# MCU.net
KiCad netlist of a schematic drawn in Altium Designer
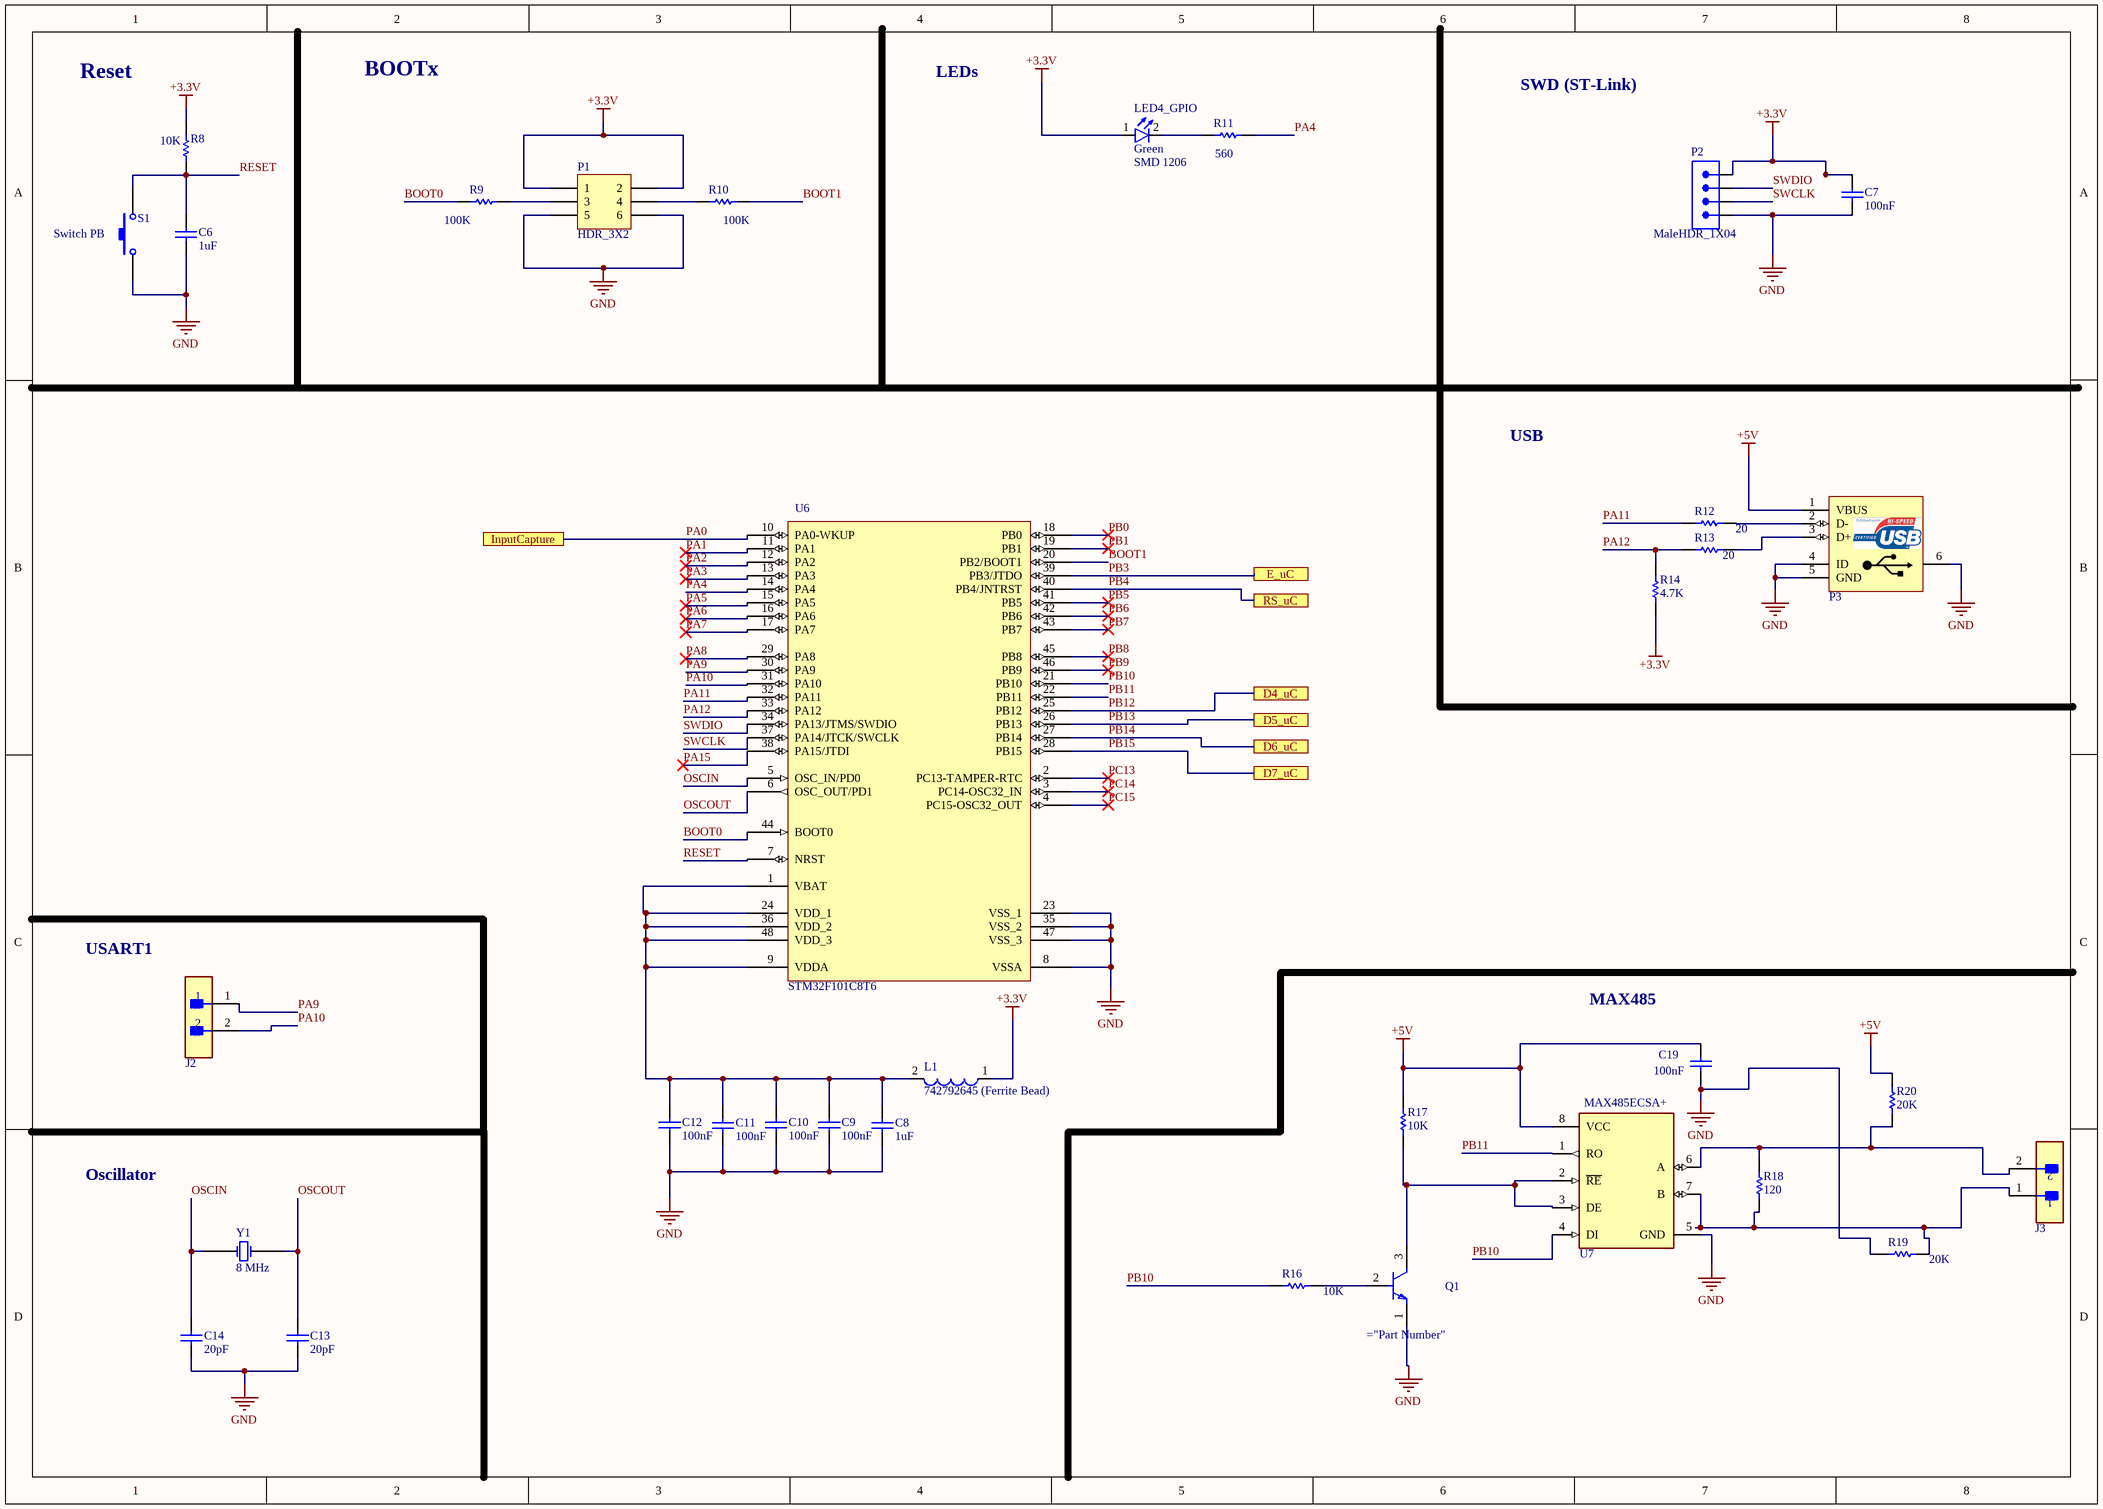
[diagram p0: MCU.SchDoc]

(export (version "E")
  (design (tool "Eeschema 10.0.6"))
  (components
    (comp (ref "C6")
      (value "1uF")
      (footprint "CAPC3216L (1206)")
      (description "Bipolar Capacitor")
      (fields
        (field (name "VOLTAGE") "100V")
        (field (name "DESIGNER") "Eng. Saeid Jorablo")
        (field (name "PUBLISHER") "SJ Unlimited")
      )
      (libsource (lib "Passive Components") (part "CAP_Bipolar"))
    )
    (comp (ref "C7")
      (value "100nF")
      (footprint "CAPC3216L (1206)")
      (description "Bipolar Capacitor")
      (fields
        (field (name "VOLTAGE") "100V")
        (field (name "DESIGNER") "Eng. Saeid Jorablo")
        (field (name "PUBLISHER") "SJ Unlimited")
      )
      (libsource (lib "Passive Components") (part "CAP_Bipolar"))
    )
    (comp (ref "C8")
      (value "1uF")
      (footprint "Cap - 100nF")
      (description "Bipolar Capacitor")
      (fields
        (field (name "VOLTAGE") "100V")
        (field (name "DESIGNER") "Eng. Saeid Jorablo")
        (field (name "PUBLISHER") "SJ Unlimited")
      )
      (libsource (lib "Passive Components") (part "CAP_Bipolar"))
    )
    (comp (ref "C9")
      (value "100nF")
      (footprint "CAPC3216M (1206)")
      (description "Bipolar Capacitor")
      (fields
        (field (name "VOLTAGE") "100V")
        (field (name "DESIGNER") "Eng. Saeid Jorablo")
        (field (name "PUBLISHER") "SJ Unlimited")
      )
      (libsource (lib "Passive Components") (part "CAP_Bipolar"))
    )
    (comp (ref "C10")
      (value "100nF")
      (footprint "CAPC3216M (1206)")
      (description "Bipolar Capacitor")
      (fields
        (field (name "VOLTAGE") "100V")
        (field (name "DESIGNER") "Eng. Saeid Jorablo")
        (field (name "PUBLISHER") "SJ Unlimited")
      )
      (libsource (lib "Passive Components") (part "CAP_Bipolar"))
    )
    (comp (ref "C11")
      (value "100nF")
      (footprint "CAPC3216M (1206)")
      (description "Bipolar Capacitor")
      (fields
        (field (name "VOLTAGE") "100V")
        (field (name "DESIGNER") "Eng. Saeid Jorablo")
        (field (name "PUBLISHER") "SJ Unlimited")
      )
      (libsource (lib "Passive Components") (part "CAP_Bipolar"))
    )
    (comp (ref "C12")
      (value "100nF")
      (footprint "CAPC3216M (1206)")
      (description "Bipolar Capacitor")
      (fields
        (field (name "VOLTAGE") "100V")
        (field (name "DESIGNER") "Eng. Saeid Jorablo")
        (field (name "PUBLISHER") "SJ Unlimited")
      )
      (libsource (lib "Passive Components") (part "CAP_Bipolar"))
    )
    (comp (ref "C13")
      (value "20pF")
      (footprint "CAPC1608M (0603)")
      (description "Bipolar Capacitor")
      (fields
        (field (name "VOLTAGE") "100V")
        (field (name "DESIGNER") "Eng. Saeid Jorablo")
        (field (name "PUBLISHER") "SJ Unlimited")
      )
      (libsource (lib "Passive Components") (part "CAP_Bipolar"))
    )
    (comp (ref "C14")
      (value "20pF")
      (footprint "CAPC1608M (0603)")
      (description "Bipolar Capacitor")
      (fields
        (field (name "VOLTAGE") "100V")
        (field (name "DESIGNER") "Eng. Saeid Jorablo")
        (field (name "PUBLISHER") "SJ Unlimited")
      )
      (libsource (lib "Passive Components") (part "CAP_Bipolar"))
    )
    (comp (ref "C19")
      (value "100nF")
      (footprint "CAPC3216M (1206)")
      (description "Bipolar Capacitor")
      (fields
        (field (name "VOLTAGE") "100V")
        (field (name "DESIGNER") "Eng. Saeid Jorablo")
        (field (name "PUBLISHER") "SJ Unlimited")
      )
      (libsource (lib "Passive Components") (part "CAP_Bipolar"))
    )
    (comp (ref "J2")
      (value "B2B-XH-A_LF_SN")
      (footprint "JST_0_MFG")
      (libsource (lib "") (part "B2B-XH-A_LF_SN_1"))
    )
    (comp (ref "J3")
      (value "B2B-XH-A_LF_SN")
      (footprint "JST_0_MFG")
      (libsource (lib "Amir_Lib") (part "B2B-XH-A_LF_SN"))
    )
    (comp (ref "L1")
      (value "742792645 (Ferrite Bead)")
      (footprint "SMD-0603")
      (description "SMD EMI Suppression Ferrite Bead WE-CBF, Z = 470 Ohm")
      (libsource (lib "Wuerth Elektronik EMC Ferrite") (part "742792645"))
    )
    (comp (ref "LED4_GPIO")
      (value "Green")
      (footprint "LED SMD 1206")
      (description "LED")
      (fields
        (field (name "COLOR") "Green")
        (field (name "SIZE") "SMD 1206")
        (field (name "DESIGNER") "Saeid Jorablo")
      )
      (libsource (lib "General 2") (part "LED"))
    )
    (comp (ref "P1")
      (value "HDR_3X2")
      (footprint "MISC_HDR_2X3")
      (description "Header, 3-Pin, Dual row")
      (fields (field (name "PUBLISHER") "SJ UnLimited") (field (name "DESIGNER") "Eng. Saeid Jorablo"))
      (libsource (lib "Sockets And Connectors") (part "HDR_3X2"))
    )
    (comp (ref "P2")
      (value "MaleHDR_1X04")
      (footprint "MHDR1X04-254P")
      (description "Male Header 1X04")
      (libsource (lib "Sockets And Connectors") (part "MHDR_1X04"))
    )
    (comp (ref "P3")
      (value "USB Connector")
      (footprint "USB_AB_BM_SHS")
      (description "USB MICRO-B Type Connector")
      (fields (field (name "DESIGNER") "ABBAS BASEREH") (field (name "PUBLISHER") "ABBAS BASEREH"))
      (libsource (lib "General 1") (part "USB AB MICRO CONNECTOR"))
    )
    (comp (ref "Q1")
      (value "2N3904TF")
      (footprint "ON_Semiconductor_135AR_MFG")
      (libsource (lib "Amir_Lib") (part "2N3904TF"))
    )
    (comp (ref "R8")
      (value "10K")
      (footprint "RESC3216X60L (1206)")
      (description "Resistor")
      (fields
        (field (name "TOLERANCE") "5%")
        (field (name "POWER") "1/8 W")
        (field (name "DESIGNER") "Eng. Saeid Jorablo")
        (field (name "PUBLISHER") "SJ Unlimited")
      )
      (libsource (lib "Passive Components") (part "RES"))
    )
    (comp (ref "R9")
      (value "100K")
      (footprint "RESC3216X60M (1206)")
      (description "Resistor")
      (fields
        (field (name "TOLERANCE") "5%")
        (field (name "POWER") "1/8 W")
        (field (name "DESIGNER") "Eng. Saeid Jorablo")
        (field (name "PUBLISHER") "SJ Unlimited")
      )
      (libsource (lib "Passive Components") (part "RES"))
    )
    (comp (ref "R10")
      (value "100K")
      (footprint "RESC3216X60M (1206)")
      (description "Resistor")
      (fields
        (field (name "TOLERANCE") "5%")
        (field (name "POWER") "1/8 W")
        (field (name "DESIGNER") "Eng. Saeid Jorablo")
        (field (name "PUBLISHER") "SJ Unlimited")
      )
      (libsource (lib "Passive Components") (part "RES"))
    )
    (comp (ref "R11")
      (value "560")
      (footprint "RESC3216X60M (1206)")
      (description "Resistor")
      (fields
        (field (name "TOLERANCE") "5%")
        (field (name "POWER") "1/8 W")
        (field (name "DESIGNER") "Eng. Saeid Jorablo")
        (field (name "PUBLISHER") "SJ Unlimited")
      )
      (libsource (lib "Passive Components") (part "RES"))
    )
    (comp (ref "R12")
      (value "20")
      (footprint "RESC3216X60M (1206)")
      (description "Resistor")
      (fields
        (field (name "TOLERANCE") "5%")
        (field (name "POWER") "1/8 W")
        (field (name "DESIGNER") "Eng. Saeid Jorablo")
        (field (name "PUBLISHER") "SJ Unlimited")
      )
      (libsource (lib "Passive Components") (part "RES"))
    )
    (comp (ref "R13")
      (value "20")
      (footprint "RESC3216X60M (1206)")
      (description "Resistor")
      (fields
        (field (name "TOLERANCE") "5%")
        (field (name "POWER") "1/8 W")
        (field (name "DESIGNER") "Eng. Saeid Jorablo")
        (field (name "PUBLISHER") "SJ Unlimited")
      )
      (libsource (lib "Passive Components") (part "RES"))
    )
    (comp (ref "R14")
      (value "4.7K")
      (footprint "RESC3216X60M (1206)")
      (description "Resistor")
      (fields
        (field (name "TOLERANCE") "5%")
        (field (name "POWER") "1/8 W")
        (field (name "DESIGNER") "Eng. Saeid Jorablo")
        (field (name "PUBLISHER") "SJ Unlimited")
      )
      (libsource (lib "Passive Components") (part "RES"))
    )
    (comp (ref "R16")
      (value "10K")
      (footprint "RESC3216X60M (1206)")
      (description "Resistor")
      (fields
        (field (name "TOLERANCE") "5%")
        (field (name "POWER") "1/8 W")
        (field (name "DESIGNER") "Eng. Saeid Jorablo")
        (field (name "PUBLISHER") "SJ Unlimited")
      )
      (libsource (lib "Passive Components") (part "RES"))
    )
    (comp (ref "R17")
      (value "10K")
      (footprint "RESC3216X60M (1206)")
      (description "Resistor")
      (fields
        (field (name "TOLERANCE") "5%")
        (field (name "POWER") "1/8 W")
        (field (name "DESIGNER") "Eng. Saeid Jorablo")
        (field (name "PUBLISHER") "SJ Unlimited")
      )
      (libsource (lib "Passive Components") (part "RES"))
    )
    (comp (ref "R18")
      (value "120")
      (footprint "RESC3216X60M (1206)")
      (description "Resistor")
      (fields
        (field (name "TOLERANCE") "5%")
        (field (name "POWER") "1/8 W")
        (field (name "DESIGNER") "Eng. Saeid Jorablo")
        (field (name "PUBLISHER") "SJ Unlimited")
      )
      (libsource (lib "Passive Components") (part "RES"))
    )
    (comp (ref "R19")
      (value "20K")
      (footprint "RESC3216X60M (1206)")
      (description "Resistor")
      (fields
        (field (name "TOLERANCE") "5%")
        (field (name "POWER") "1/8 W")
        (field (name "DESIGNER") "Eng. Saeid Jorablo")
        (field (name "PUBLISHER") "SJ Unlimited")
      )
      (libsource (lib "Passive Components") (part "RES"))
    )
    (comp (ref "R20")
      (value "20K")
      (footprint "RESC3216X60M (1206)")
      (description "Resistor")
      (fields
        (field (name "TOLERANCE") "5%")
        (field (name "POWER") "1/8 W")
        (field (name "DESIGNER") "Eng. Saeid Jorablo")
        (field (name "PUBLISHER") "SJ Unlimited")
      )
      (libsource (lib "Passive Components") (part "RES"))
    )
    (comp (ref "S1")
      (value "Switch PB")
      (footprint "Switch - Push to On")
      (description "Push Button Switch")
      (libsource (lib "General 2") (part "Switch PB"))
    )
    (comp (ref "U6")
      (value "STM32F101C8T6")
      (footprint "LQFP48_L")
      (description "STM32 ARM-based 32-bit MCU with 64 Kbytes Flash, 48-pin LQFP, Industrial Temperature")
      (fields (field (name "PUBLISHER") "Altium Limited"))
      (libsource (lib "ST Microcontroller 32-Bit STM32") (part "STM32F101C8T6"))
    )
    (comp (ref "U7")
      (value "MAX485ECSA+")
      (footprint "Maxim_Integrated_S8-5_MFG")
      (libsource (lib "Amir_Lib") (part "MAX485ECSA+"))
    )
    (comp (ref "Y1")
      (value "8 MHz")
      (footprint "Crystal SMD")
      (description "XTAL Crystal")
      (fields (field (name "DESIGNER") "ABBAS BASEREH"))
      (libsource (lib "General 1") (part "XTAL_Crystal"))
    )
  )
  (nets
    (net (code "1") (name "+3.3V") (class "Default")
      (node (ref "C7") (pin "1") (pinfunction "+_1") (pintype "passive"))
      (node (ref "L1") (pin "1") (pinfunction "1_1") (pintype "passive"))
      (node (ref "LED4_GPIO") (pin "1") (pinfunction "A_1") (pintype "passive"))
      (node (ref "P1") (pin "1") (pinfunction "1_1") (pintype "passive"))
      (node (ref "P1") (pin "2") (pinfunction "2_2") (pintype "passive"))
      (node (ref "P2") (pin "4") (pinfunction "4_4") (pintype "passive"))
      (node (ref "R14") (pin "1") (pinfunction "1_1") (pintype "passive"))
      (node (ref "R8") (pin "2") (pinfunction "2_2") (pintype "passive"))
    )
    (net (code "2") (name "+5V") (class "Default")
      (node (ref "C19") (pin "2") (pinfunction "-_2") (pintype "passive"))
      (node (ref "P3") (pin "1") (pinfunction "VBUS_1") (pintype "power_in"))
      (node (ref "R17") (pin "2") (pinfunction "2_2") (pintype "passive"))
      (node (ref "R20") (pin "2") (pinfunction "2_2") (pintype "passive"))
      (node (ref "U7") (pin "8") (pinfunction "VCC_8") (pintype "power_in"))
    )
    (net (code "3") (name "/BOOT0") (class "Default")
      (node (ref "R9") (pin "1") (pinfunction "1_1") (pintype "passive"))
      (node (ref "U6") (pin "44") (pinfunction "BOOT0_44") (pintype "input"))
    )
    (net (code "4") (name "/BOOT1") (class "Default")
      (node (ref "R10") (pin "2") (pinfunction "2_2") (pintype "passive"))
      (node (ref "U6") (pin "20") (pinfunction "PB2/BOOT1_20") (pintype "bidirectional"))
    )
    (net (code "5") (name "/OSCIN") (class "Default")
      (node (ref "C14") (pin "1") (pinfunction "+_1") (pintype "passive"))
      (node (ref "U6") (pin "5") (pinfunction "OSC_IN/PD0_5") (pintype "input"))
      (node (ref "Y1") (pin "1") (pinfunction "OSC1_1") (pintype "passive"))
    )
    (net (code "6") (name "/OSCOUT") (class "Default")
      (node (ref "C13") (pin "1") (pinfunction "+_1") (pintype "passive"))
      (node (ref "U6") (pin "6") (pinfunction "OSC_OUT/PD1_6") (pintype "output"))
      (node (ref "Y1") (pin "2") (pinfunction "OSC2_2") (pintype "passive"))
    )
    (net (code "7") (name "/PA0") (class "Default")
      (node (ref "U6") (pin "10") (pinfunction "PA0-WKUP_10") (pintype "bidirectional"))
    )
    (net (code "8") (name "/PA1") (class "Default")
      (node (ref "U6") (pin "11") (pinfunction "PA1_11") (pintype "bidirectional+no_connect"))
    )
    (net (code "9") (name "/PA2") (class "Default")
      (node (ref "U6") (pin "12") (pinfunction "PA2_12") (pintype "bidirectional+no_connect"))
    )
    (net (code "10") (name "/PA3") (class "Default")
      (node (ref "U6") (pin "13") (pinfunction "PA3_13") (pintype "bidirectional+no_connect"))
    )
    (net (code "11") (name "/PA4") (class "Default")
      (node (ref "R11") (pin "2") (pinfunction "2_2") (pintype "passive"))
      (node (ref "U6") (pin "14") (pinfunction "PA4_14") (pintype "bidirectional"))
    )
    (net (code "12") (name "/PA5") (class "Default")
      (node (ref "U6") (pin "15") (pinfunction "PA5_15") (pintype "bidirectional+no_connect"))
    )
    (net (code "13") (name "/PA6") (class "Default")
      (node (ref "U6") (pin "16") (pinfunction "PA6_16") (pintype "bidirectional+no_connect"))
    )
    (net (code "14") (name "/PA7") (class "Default")
      (node (ref "U6") (pin "17") (pinfunction "PA7_17") (pintype "bidirectional+no_connect"))
    )
    (net (code "15") (name "/PA8") (class "Default")
      (node (ref "U6") (pin "29") (pinfunction "PA8_29") (pintype "bidirectional+no_connect"))
    )
    (net (code "16") (name "/PA9") (class "Default")
      (node (ref "J2") (pin "1") (pinfunction "1_1") (pintype "passive"))
      (node (ref "U6") (pin "30") (pinfunction "PA9_30") (pintype "bidirectional"))
    )
    (net (code "17") (name "/PA10") (class "Default")
      (node (ref "J2") (pin "2") (pinfunction "2_2") (pintype "passive"))
      (node (ref "U6") (pin "31") (pinfunction "PA10_31") (pintype "bidirectional"))
    )
    (net (code "18") (name "/PA11") (class "Default")
      (node (ref "R12") (pin "1") (pinfunction "1_1") (pintype "passive"))
      (node (ref "U6") (pin "32") (pinfunction "PA11_32") (pintype "bidirectional"))
    )
    (net (code "19") (name "/PA12") (class "Default")
      (node (ref "R13") (pin "1") (pinfunction "1_1") (pintype "passive"))
      (node (ref "R14") (pin "2") (pinfunction "2_2") (pintype "passive"))
      (node (ref "U6") (pin "33") (pinfunction "PA12_33") (pintype "bidirectional"))
    )
    (net (code "20") (name "/PA15") (class "Default")
      (node (ref "U6") (pin "38") (pinfunction "PA15/JTDI_38") (pintype "bidirectional+no_connect"))
    )
    (net (code "21") (name "/PB0") (class "Default")
      (node (ref "U6") (pin "18") (pinfunction "PB0_18") (pintype "bidirectional+no_connect"))
    )
    (net (code "22") (name "/PB1") (class "Default")
      (node (ref "U6") (pin "19") (pinfunction "PB1_19") (pintype "bidirectional+no_connect"))
    )
    (net (code "23") (name "/PB3") (class "Default")
      (node (ref "U6") (pin "39") (pinfunction "PB3/JTDO_39") (pintype "bidirectional"))
    )
    (net (code "24") (name "/PB4") (class "Default")
      (node (ref "U6") (pin "40") (pinfunction "PB4/JNTRST_40") (pintype "bidirectional"))
    )
    (net (code "25") (name "/PB5") (class "Default")
      (node (ref "U6") (pin "41") (pinfunction "PB5_41") (pintype "bidirectional+no_connect"))
    )
    (net (code "26") (name "/PB6") (class "Default")
      (node (ref "U6") (pin "42") (pinfunction "PB6_42") (pintype "bidirectional+no_connect"))
    )
    (net (code "27") (name "/PB7") (class "Default")
      (node (ref "U6") (pin "43") (pinfunction "PB7_43") (pintype "bidirectional+no_connect"))
    )
    (net (code "28") (name "/PB8") (class "Default")
      (node (ref "U6") (pin "45") (pinfunction "PB8_45") (pintype "bidirectional+no_connect"))
    )
    (net (code "29") (name "/PB9") (class "Default")
      (node (ref "U6") (pin "46") (pinfunction "PB9_46") (pintype "bidirectional+no_connect"))
    )
    (net (code "30") (name "/PB10") (class "Default")
      (node (ref "R16") (pin "1") (pinfunction "1_1") (pintype "passive"))
      (node (ref "U6") (pin "21") (pinfunction "PB10_21") (pintype "bidirectional"))
      (node (ref "U7") (pin "4") (pinfunction "DI_4") (pintype "input"))
    )
    (net (code "31") (name "/PB11") (class "Default")
      (node (ref "U6") (pin "22") (pinfunction "PB11_22") (pintype "bidirectional"))
      (node (ref "U7") (pin "1") (pinfunction "RO_1") (pintype "output"))
    )
    (net (code "32") (name "/PB12") (class "Default")
      (node (ref "U6") (pin "25") (pinfunction "PB12_25") (pintype "bidirectional"))
    )
    (net (code "33") (name "/PB13") (class "Default")
      (node (ref "U6") (pin "26") (pinfunction "PB13_26") (pintype "bidirectional"))
    )
    (net (code "34") (name "/PB14") (class "Default")
      (node (ref "U6") (pin "27") (pinfunction "PB14_27") (pintype "bidirectional"))
    )
    (net (code "35") (name "/PB15") (class "Default")
      (node (ref "U6") (pin "28") (pinfunction "PB15_28") (pintype "bidirectional"))
    )
    (net (code "36") (name "/PC13") (class "Default")
      (node (ref "U6") (pin "2") (pinfunction "PC13-TAMPER-RTC_2") (pintype "bidirectional+no_connect"))
    )
    (net (code "37") (name "/PC14") (class "Default")
      (node (ref "U6") (pin "3") (pinfunction "PC14-OSC32_IN_3") (pintype "bidirectional+no_connect"))
    )
    (net (code "38") (name "/PC15") (class "Default")
      (node (ref "U6") (pin "4") (pinfunction "PC15-OSC32_OUT_4") (pintype "bidirectional+no_connect"))
    )
    (net (code "39") (name "/RESET") (class "Default")
      (node (ref "C6") (pin "1") (pinfunction "+_1") (pintype "passive"))
      (node (ref "R8") (pin "1") (pinfunction "1_1") (pintype "passive"))
      (node (ref "S1") (pin "2") (pinfunction "2_2") (pintype "passive"))
      (node (ref "U6") (pin "7") (pinfunction "NRST_7") (pintype "bidirectional"))
    )
    (net (code "40") (name "/SWCLK") (class "Default")
      (node (ref "P2") (pin "2") (pinfunction "2_2") (pintype "passive"))
      (node (ref "U6") (pin "37") (pinfunction "PA14/JTCK/SWCLK_37") (pintype "bidirectional"))
    )
    (net (code "41") (name "/SWDIO") (class "Default")
      (node (ref "P2") (pin "3") (pinfunction "3_3") (pintype "passive"))
      (node (ref "U6") (pin "34") (pinfunction "PA13/JTMS/SWDIO_34") (pintype "bidirectional"))
    )
    (net (code "42") (name "GND") (class "Default")
      (node (ref "C10") (pin "2") (pinfunction "-_2") (pintype "passive"))
      (node (ref "C11") (pin "2") (pinfunction "-_2") (pintype "passive"))
      (node (ref "C12") (pin "2") (pinfunction "-_2") (pintype "passive"))
      (node (ref "C13") (pin "2") (pinfunction "-_2") (pintype "passive"))
      (node (ref "C14") (pin "2") (pinfunction "-_2") (pintype "passive"))
      (node (ref "C19") (pin "1") (pinfunction "+_1") (pintype "passive"))
      (node (ref "C6") (pin "2") (pinfunction "-_2") (pintype "passive"))
      (node (ref "C7") (pin "2") (pinfunction "-_2") (pintype "passive"))
      (node (ref "C8") (pin "2") (pinfunction "-_2") (pintype "passive"))
      (node (ref "C9") (pin "2") (pinfunction "-_2") (pintype "passive"))
      (node (ref "P1") (pin "5") (pinfunction "5_5") (pintype "passive"))
      (node (ref "P1") (pin "6") (pinfunction "6_6") (pintype "passive"))
      (node (ref "P2") (pin "1") (pinfunction "1_1") (pintype "passive"))
      (node (ref "P3") (pin "4") (pinfunction "ID_4") (pintype "power_in"))
      (node (ref "P3") (pin "5") (pinfunction "GND_5") (pintype "power_in"))
      (node (ref "P3") (pin "6") (pinfunction "MH_6") (pintype "power_in"))
      (node (ref "Q1") (pin "1") (pinfunction "E_1") (pintype "passive"))
      (node (ref "R19") (pin "1") (pinfunction "1_1") (pintype "passive"))
      (node (ref "S1") (pin "1") (pinfunction "1_1") (pintype "passive"))
      (node (ref "U6") (pin "23") (pinfunction "VSS_1_23") (pintype "power_in"))
      (node (ref "U6") (pin "35") (pinfunction "VSS_2_35") (pintype "power_in"))
      (node (ref "U6") (pin "47") (pinfunction "VSS_3_47") (pintype "power_in"))
      (node (ref "U6") (pin "8") (pinfunction "VSSA_8") (pintype "power_in"))
      (node (ref "U7") (pin "5") (pinfunction "GND_5") (pintype "power_in"))
    )
    (net (code "43") (name "Net-(C10-+)") (class "Default")
      (node (ref "C10") (pin "1") (pinfunction "+_1") (pintype "passive"))
      (node (ref "C11") (pin "1") (pinfunction "+_1") (pintype "passive"))
      (node (ref "C12") (pin "1") (pinfunction "+_1") (pintype "passive"))
      (node (ref "C8") (pin "1") (pinfunction "+_1") (pintype "passive"))
      (node (ref "C9") (pin "1") (pinfunction "+_1") (pintype "passive"))
      (node (ref "L1") (pin "2") (pinfunction "2_2") (pintype "passive"))
      (node (ref "U6") (pin "1") (pinfunction "VBAT_1") (pintype "power_in"))
      (node (ref "U6") (pin "24") (pinfunction "VDD_1_24") (pintype "power_in"))
      (node (ref "U6") (pin "36") (pinfunction "VDD_2_36") (pintype "power_in"))
      (node (ref "U6") (pin "48") (pinfunction "VDD_3_48") (pintype "power_in"))
      (node (ref "U6") (pin "9") (pinfunction "VDDA_9") (pintype "power_in"))
    )
    (net (code "44") (name "Net-(LED4_GPIO-K)") (class "Default")
      (node (ref "LED4_GPIO") (pin "2") (pinfunction "K_2") (pintype "passive"))
      (node (ref "R11") (pin "1") (pinfunction "1_1") (pintype "passive"))
    )
    (net (code "45") (name "Net-(P1-Pad3)") (class "Default")
      (node (ref "P1") (pin "3") (pinfunction "3_3") (pintype "passive"))
      (node (ref "R9") (pin "2") (pinfunction "2_2") (pintype "passive"))
    )
    (net (code "46") (name "Net-(P1-Pad4)") (class "Default")
      (node (ref "P1") (pin "4") (pinfunction "4_4") (pintype "passive"))
      (node (ref "R10") (pin "1") (pinfunction "1_1") (pintype "passive"))
    )
    (net (code "47") (name "Net-(P3-D+)") (class "Default")
      (node (ref "P3") (pin "3") (pinfunction "D+_3") (pintype "bidirectional"))
      (node (ref "R13") (pin "2") (pinfunction "2_2") (pintype "passive"))
    )
    (net (code "48") (name "Net-(P3-D-)") (class "Default")
      (node (ref "P3") (pin "2") (pinfunction "D-_2") (pintype "bidirectional"))
      (node (ref "R12") (pin "2") (pinfunction "2_2") (pintype "passive"))
    )
    (net (code "49") (name "Net-(Q1-B)") (class "Default")
      (node (ref "Q1") (pin "2") (pinfunction "B_2") (pintype "passive"))
      (node (ref "R16") (pin "2") (pinfunction "2_2") (pintype "passive"))
    )
    (net (code "50") (name "Net-(Q1-C)") (class "Default")
      (node (ref "Q1") (pin "3") (pinfunction "C_3") (pintype "passive"))
      (node (ref "R17") (pin "1") (pinfunction "1_1") (pintype "passive"))
      (node (ref "U7") (pin "2") (pinfunction "~{RE}_2") (pintype "input"))
      (node (ref "U7") (pin "3") (pinfunction "DE_3") (pintype "input"))
    )
    (net (code "51") (name "Net-(U7-A)") (class "Default")
      (node (ref "J3") (pin "2") (pinfunction "2_2") (pintype "passive"))
      (node (ref "R18") (pin "2") (pinfunction "2_2") (pintype "passive"))
      (node (ref "R20") (pin "1") (pinfunction "1_1") (pintype "passive"))
      (node (ref "U7") (pin "6") (pinfunction "A_6") (pintype "bidirectional"))
    )
    (net (code "52") (name "Net-(U7-B)") (class "Default")
      (node (ref "J3") (pin "1") (pinfunction "1_1") (pintype "passive"))
      (node (ref "R18") (pin "1") (pinfunction "1_1") (pintype "passive"))
      (node (ref "R19") (pin "2") (pinfunction "2_2") (pintype "passive"))
      (node (ref "U7") (pin "7") (pinfunction "B_7") (pintype "bidirectional"))
    )
  )
)
